# LAN_WIZ_V0_1a.net
KiCad netlist of a schematic drawn in EAGLE
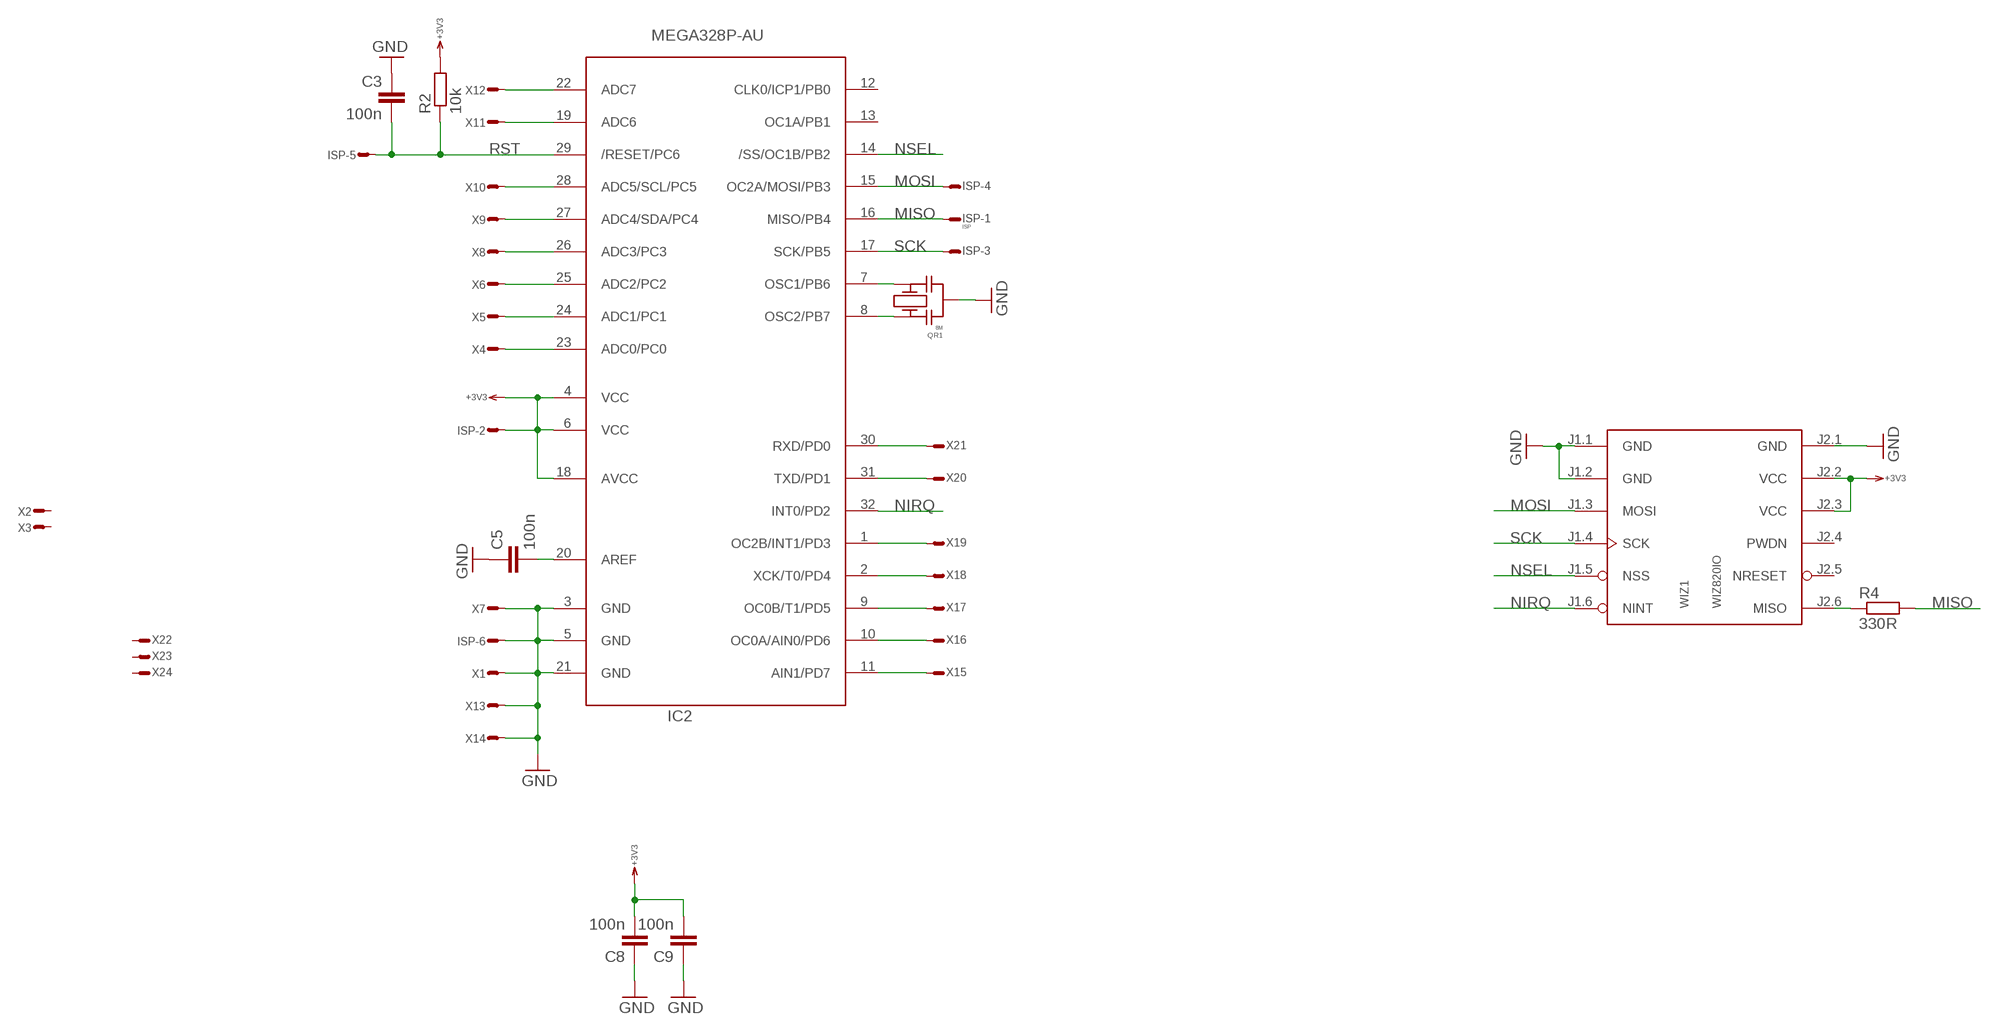
[diagram p0: schematic, sheet 1]

(export (version "E")
  (design (tool "Eeschema 10.0.6"))
  (components
    (comp (ref "C3")
      (value "100n")
      (footprint "eagle-import:0603")
      (libsource (lib "eagle-import") (part "C0603"))
    )
    (comp (ref "C5")
      (value "100n")
      (footprint "eagle-import:0603")
      (libsource (lib "eagle-import") (part "C0603"))
    )
    (comp (ref "C8")
      (value "100n")
      (footprint "eagle-import:0603")
      (libsource (lib "eagle-import") (part "C0603"))
    )
    (comp (ref "C9")
      (value "100n")
      (footprint "eagle-import:0603")
      (libsource (lib "eagle-import") (part "C0603"))
    )
    (comp (ref "IC2")
      (value "MEGA328P-AU")
      (footprint "eagle-import:TQFP32-08")
      (libsource (lib "eagle-import") (part "MEGA168PA"))
    )
    (comp (ref "ISP")
      (value "ISP")
      (footprint "eagle-import:ML6S")
      (libsource (lib "eagle-import") (part "ML6ES"))
    )
    (comp (ref "QR1")
      (value "8M")
      (footprint "eagle-import:CR")
      (libsource (lib "eagle-import") (part "QRCR"))
    )
    (comp (ref "R2")
      (value "10k")
      (footprint "eagle-import:0603")
      (libsource (lib "eagle-import") (part "R0603"))
    )
    (comp (ref "R4")
      (value "330R")
      (footprint "eagle-import:0603")
      (libsource (lib "eagle-import") (part "R0603"))
    )
    (comp (ref "WIZ1")
      (value "WIZ820IO")
      (footprint "eagle-import:WIZ820IO")
      (libsource (lib "eagle-import") (part "WIZ820IO"))
    )
    (comp (ref "X1")
      (value "WIREPADT1.6/0.9")
      (footprint "eagle-import:T1.6_0.9")
      (libsource (lib "eagle-import") (part "WIREPADT1.6/0.9"))
    )
    (comp (ref "X2")
      (value "WIREPADT1.6/0.9")
      (footprint "eagle-import:T1.6_0.9")
      (libsource (lib "eagle-import") (part "WIREPADT1.6/0.9"))
    )
    (comp (ref "X3")
      (value "WIREPADT1.6/0.9")
      (footprint "eagle-import:T1.6_0.9")
      (libsource (lib "eagle-import") (part "WIREPADT1.6/0.9"))
    )
    (comp (ref "X4")
      (value "WIREPADT1.6/0.9")
      (footprint "eagle-import:T1.6_0.9")
      (libsource (lib "eagle-import") (part "WIREPADT1.6/0.9"))
    )
    (comp (ref "X5")
      (value "WIREPADT1.6/0.9")
      (footprint "eagle-import:T1.6_0.9")
      (libsource (lib "eagle-import") (part "WIREPADT1.6/0.9"))
    )
    (comp (ref "X6")
      (value "WIREPADT1.6/0.9")
      (footprint "eagle-import:T1.6_0.9")
      (libsource (lib "eagle-import") (part "WIREPADT1.6/0.9"))
    )
    (comp (ref "X7")
      (value "WIREPADT1.6/0.9")
      (footprint "eagle-import:T1.6_0.9")
      (libsource (lib "eagle-import") (part "WIREPADT1.6/0.9"))
    )
    (comp (ref "X8")
      (value "WIREPADT1.6/0.9")
      (footprint "eagle-import:T1.6_0.9")
      (libsource (lib "eagle-import") (part "WIREPADT1.6/0.9"))
    )
    (comp (ref "X9")
      (value "WIREPADT1.6/0.9")
      (footprint "eagle-import:T1.6_0.9")
      (libsource (lib "eagle-import") (part "WIREPADT1.6/0.9"))
    )
    (comp (ref "X10")
      (value "WIREPADT1.6/0.9")
      (footprint "eagle-import:T1.6_0.9")
      (libsource (lib "eagle-import") (part "WIREPADT1.6/0.9"))
    )
    (comp (ref "X11")
      (value "WIREPADT1.6/0.9")
      (footprint "eagle-import:T1.6_0.9")
      (libsource (lib "eagle-import") (part "WIREPADT1.6/0.9"))
    )
    (comp (ref "X12")
      (value "WIREPADT1.6/0.9")
      (footprint "eagle-import:T1.6_0.9")
      (libsource (lib "eagle-import") (part "WIREPADT1.6/0.9"))
    )
    (comp (ref "X13")
      (value "WIREPADT1.6/0.9")
      (footprint "eagle-import:T1.6_0.9")
      (libsource (lib "eagle-import") (part "WIREPADT1.6/0.9"))
    )
    (comp (ref "X14")
      (value "WIREPADT1.6/0.9")
      (footprint "eagle-import:T1.6_0.9")
      (libsource (lib "eagle-import") (part "WIREPADT1.6/0.9"))
    )
    (comp (ref "X15")
      (value "WIREPADT1.6/0.9")
      (footprint "eagle-import:T1.6_0.9")
      (libsource (lib "eagle-import") (part "WIREPADT1.6/0.9"))
    )
    (comp (ref "X16")
      (value "WIREPADT1.6/0.9")
      (footprint "eagle-import:T1.6_0.9")
      (libsource (lib "eagle-import") (part "WIREPADT1.6/0.9"))
    )
    (comp (ref "X17")
      (value "WIREPADT1.6/0.9")
      (footprint "eagle-import:T1.6_0.9")
      (libsource (lib "eagle-import") (part "WIREPADT1.6/0.9"))
    )
    (comp (ref "X18")
      (value "WIREPADT1.6/0.9")
      (footprint "eagle-import:T1.6_0.9")
      (libsource (lib "eagle-import") (part "WIREPADT1.6/0.9"))
    )
    (comp (ref "X19")
      (value "WIREPADT1.6/0.9")
      (footprint "eagle-import:T1.6_0.9")
      (libsource (lib "eagle-import") (part "WIREPADT1.6/0.9"))
    )
    (comp (ref "X20")
      (value "WIREPADT1.6/0.9")
      (footprint "eagle-import:T1.6_0.9")
      (libsource (lib "eagle-import") (part "WIREPADT1.6/0.9"))
    )
    (comp (ref "X21")
      (value "WIREPADT1.6/0.9")
      (footprint "eagle-import:T1.6_0.9")
      (libsource (lib "eagle-import") (part "WIREPADT1.6/0.9"))
    )
    (comp (ref "X22")
      (value "WIREPADT1.6/0.9")
      (footprint "eagle-import:T1.6_0.9")
      (libsource (lib "eagle-import") (part "WIREPADT1.6/0.9"))
    )
    (comp (ref "X23")
      (value "WIREPADT1.6/0.9")
      (footprint "eagle-import:T1.6_0.9")
      (libsource (lib "eagle-import") (part "WIREPADT1.6/0.9"))
    )
    (comp (ref "X24")
      (value "WIREPADT1.6/0.9")
      (footprint "eagle-import:T1.6_0.9")
      (libsource (lib "eagle-import") (part "WIREPADT1.6/0.9"))
    )
  )
  (nets
    (net (code "1") (name "+3V3") (class "Default")
      (node (ref "C8") (pin "2") (pinfunction "2_2") (pintype "passive"))
      (node (ref "C9") (pin "2") (pinfunction "2_2") (pintype "passive"))
      (node (ref "IC2") (pin "18") (pinfunction "AVCC_18") (pintype "bidirectional"))
      (node (ref "IC2") (pin "4") (pinfunction "VCC_4") (pintype "bidirectional"))
      (node (ref "IC2") (pin "6") (pinfunction "VCC_6") (pintype "bidirectional"))
      (node (ref "ISP") (pin "2") (pinfunction "S_2") (pintype "passive"))
      (node (ref "R2") (pin "2") (pinfunction "2_2") (pintype "passive"))
      (node (ref "WIZ1") (pin "J2.2") (pinfunction "VCC_J2.2") (pintype "bidirectional"))
      (node (ref "WIZ1") (pin "J2.3") (pinfunction "VCC_J2.3") (pintype "bidirectional"))
    )
    (net (code "2") (name "/MISO") (class "Default")
      (node (ref "IC2") (pin "16") (pinfunction "MISO/PB4_16") (pintype "bidirectional"))
      (node (ref "ISP") (pin "1") (pinfunction "S_1") (pintype "passive"))
      (node (ref "R4") (pin "2") (pinfunction "2_2") (pintype "passive"))
    )
    (net (code "3") (name "/MOSI") (class "Default")
      (node (ref "IC2") (pin "15") (pinfunction "OC2A/MOSI/PB3_15") (pintype "bidirectional"))
      (node (ref "ISP") (pin "4") (pinfunction "S_4") (pintype "passive"))
      (node (ref "WIZ1") (pin "J1.3") (pinfunction "MOSI_J1.3") (pintype "input"))
    )
    (net (code "4") (name "/NIRQ") (class "Default")
      (node (ref "IC2") (pin "32") (pinfunction "INT0/PD2_32") (pintype "bidirectional"))
      (node (ref "WIZ1") (pin "J1.6") (pinfunction "NINT_J1.6") (pintype "output"))
    )
    (net (code "5") (name "/NSEL") (class "Default")
      (node (ref "IC2") (pin "14") (pinfunction "/SS/OC1B/PB2_14") (pintype "bidirectional"))
      (node (ref "WIZ1") (pin "J1.5") (pinfunction "NSS_J1.5") (pintype "input"))
    )
    (net (code "6") (name "/RST") (class "Default")
      (node (ref "C3") (pin "2") (pinfunction "2_2") (pintype "passive"))
      (node (ref "IC2") (pin "29") (pinfunction "/RESET/PC6_29") (pintype "bidirectional"))
      (node (ref "ISP") (pin "5") (pinfunction "S_5") (pintype "passive"))
      (node (ref "R2") (pin "1") (pinfunction "1_1") (pintype "passive"))
    )
    (net (code "7") (name "/SCK") (class "Default")
      (node (ref "IC2") (pin "17") (pinfunction "SCK/PB5_17") (pintype "bidirectional"))
      (node (ref "ISP") (pin "3") (pinfunction "S_3") (pintype "passive"))
      (node (ref "WIZ1") (pin "J1.4") (pinfunction "SCK_J1.4") (pintype "input"))
    )
    (net (code "8") (name "GND") (class "Default")
      (node (ref "C3") (pin "1") (pinfunction "1_1") (pintype "passive"))
      (node (ref "C5") (pin "1") (pinfunction "1_1") (pintype "passive"))
      (node (ref "C8") (pin "1") (pinfunction "1_1") (pintype "passive"))
      (node (ref "C9") (pin "1") (pinfunction "1_1") (pintype "passive"))
      (node (ref "IC2") (pin "21") (pinfunction "GND_21") (pintype "bidirectional"))
      (node (ref "IC2") (pin "3") (pinfunction "GND_3") (pintype "bidirectional"))
      (node (ref "IC2") (pin "5") (pinfunction "GND_5") (pintype "bidirectional"))
      (node (ref "ISP") (pin "6") (pinfunction "S_6") (pintype "passive"))
      (node (ref "QR1") (pin "M") (pinfunction "M_M") (pintype "passive"))
      (node (ref "WIZ1") (pin "J1.1") (pinfunction "GND_J1.1") (pintype "bidirectional"))
      (node (ref "WIZ1") (pin "J1.2") (pinfunction "GND_J1.2") (pintype "bidirectional"))
      (node (ref "WIZ1") (pin "J2.1") (pinfunction "GND_J2.1") (pintype "bidirectional"))
      (node (ref "X1") (pin "1") (pinfunction "S_1") (pintype "passive"))
      (node (ref "X13") (pin "1") (pinfunction "S_1") (pintype "passive"))
      (node (ref "X14") (pin "1") (pinfunction "S_1") (pintype "passive"))
      (node (ref "X7") (pin "1") (pinfunction "S_1") (pintype "passive"))
    )
    (net (code "9") (name "Net-(IC2-ADC0{slash}PC0)") (class "Default")
      (node (ref "IC2") (pin "23") (pinfunction "ADC0/PC0_23") (pintype "bidirectional"))
      (node (ref "X4") (pin "1") (pinfunction "S_1") (pintype "passive"))
    )
    (net (code "10") (name "Net-(IC2-ADC1{slash}PC1)") (class "Default")
      (node (ref "IC2") (pin "24") (pinfunction "ADC1/PC1_24") (pintype "bidirectional"))
      (node (ref "X5") (pin "1") (pinfunction "S_1") (pintype "passive"))
    )
    (net (code "11") (name "Net-(IC2-ADC2{slash}PC2)") (class "Default")
      (node (ref "IC2") (pin "25") (pinfunction "ADC2/PC2_25") (pintype "bidirectional"))
      (node (ref "X6") (pin "1") (pinfunction "S_1") (pintype "passive"))
    )
    (net (code "12") (name "Net-(IC2-ADC3{slash}PC3)") (class "Default")
      (node (ref "IC2") (pin "26") (pinfunction "ADC3/PC3_26") (pintype "bidirectional"))
      (node (ref "X8") (pin "1") (pinfunction "S_1") (pintype "passive"))
    )
    (net (code "13") (name "Net-(IC2-ADC4{slash}SDA{slash}PC4)") (class "Default")
      (node (ref "IC2") (pin "27") (pinfunction "ADC4/SDA/PC4_27") (pintype "bidirectional"))
      (node (ref "X9") (pin "1") (pinfunction "S_1") (pintype "passive"))
    )
    (net (code "14") (name "Net-(IC2-ADC5{slash}SCL{slash}PC5)") (class "Default")
      (node (ref "IC2") (pin "28") (pinfunction "ADC5/SCL/PC5_28") (pintype "bidirectional"))
      (node (ref "X10") (pin "1") (pinfunction "S_1") (pintype "passive"))
    )
    (net (code "15") (name "Net-(IC2-ADC6)") (class "Default")
      (node (ref "IC2") (pin "19") (pinfunction "ADC6_19") (pintype "bidirectional"))
      (node (ref "X11") (pin "1") (pinfunction "S_1") (pintype "passive"))
    )
    (net (code "16") (name "Net-(IC2-ADC7)") (class "Default")
      (node (ref "IC2") (pin "22") (pinfunction "ADC7_22") (pintype "bidirectional"))
      (node (ref "X12") (pin "1") (pinfunction "S_1") (pintype "passive"))
    )
    (net (code "17") (name "Net-(IC2-AIN1{slash}PD7)") (class "Default")
      (node (ref "IC2") (pin "11") (pinfunction "AIN1/PD7_11") (pintype "bidirectional"))
      (node (ref "X15") (pin "1") (pinfunction "S_1") (pintype "passive"))
    )
    (net (code "18") (name "Net-(IC2-AREF)") (class "Default")
      (node (ref "C5") (pin "2") (pinfunction "2_2") (pintype "passive"))
      (node (ref "IC2") (pin "20") (pinfunction "AREF_20") (pintype "bidirectional"))
    )
    (net (code "19") (name "Net-(IC2-OC0A{slash}AIN0{slash}PD6)") (class "Default")
      (node (ref "IC2") (pin "10") (pinfunction "OC0A/AIN0/PD6_10") (pintype "bidirectional"))
      (node (ref "X16") (pin "1") (pinfunction "S_1") (pintype "passive"))
    )
    (net (code "20") (name "Net-(IC2-OC0B{slash}T1{slash}PD5)") (class "Default")
      (node (ref "IC2") (pin "9") (pinfunction "OC0B/T1/PD5_9") (pintype "bidirectional"))
      (node (ref "X17") (pin "1") (pinfunction "S_1") (pintype "passive"))
    )
    (net (code "21") (name "Net-(IC2-OC2B{slash}INT1{slash}PD3)") (class "Default")
      (node (ref "IC2") (pin "1") (pinfunction "OC2B/INT1/PD3_1") (pintype "bidirectional"))
      (node (ref "X19") (pin "1") (pinfunction "S_1") (pintype "passive"))
    )
    (net (code "22") (name "Net-(IC2-OSC1{slash}PB6)") (class "Default")
      (node (ref "IC2") (pin "7") (pinfunction "OSC1/PB6_7") (pintype "bidirectional"))
      (node (ref "QR1") (pin "2") (pinfunction "2_2") (pintype "passive"))
    )
    (net (code "23") (name "Net-(IC2-OSC2{slash}PB7)") (class "Default")
      (node (ref "IC2") (pin "8") (pinfunction "OSC2/PB7_8") (pintype "bidirectional"))
      (node (ref "QR1") (pin "1") (pinfunction "1_1") (pintype "passive"))
    )
    (net (code "24") (name "Net-(IC2-RXD{slash}PD0)") (class "Default")
      (node (ref "IC2") (pin "30") (pinfunction "RXD/PD0_30") (pintype "bidirectional"))
      (node (ref "X21") (pin "1") (pinfunction "S_1") (pintype "passive"))
    )
    (net (code "25") (name "Net-(IC2-TXD{slash}PD1)") (class "Default")
      (node (ref "IC2") (pin "31") (pinfunction "TXD/PD1_31") (pintype "bidirectional"))
      (node (ref "X20") (pin "1") (pinfunction "S_1") (pintype "passive"))
    )
    (net (code "26") (name "Net-(IC2-XCK{slash}T0{slash}PD4)") (class "Default")
      (node (ref "IC2") (pin "2") (pinfunction "XCK/T0/PD4_2") (pintype "bidirectional"))
      (node (ref "X18") (pin "1") (pinfunction "S_1") (pintype "passive"))
    )
    (net (code "27") (name "Net-(WIZ1-MISO)") (class "Default")
      (node (ref "R4") (pin "1") (pinfunction "1_1") (pintype "passive"))
      (node (ref "WIZ1") (pin "J2.6") (pinfunction "MISO_J2.6") (pintype "output"))
    )
    (net (code "28") (name "unconnected-(IC2-CLK0{slash}ICP1{slash}PB0-Pad12)") (class "Default")
      (node (ref "IC2") (pin "12") (pinfunction "CLK0/ICP1/PB0_12") (pintype "bidirectional"))
    )
    (net (code "29") (name "unconnected-(IC2-OC1A{slash}PB1-Pad13)") (class "Default")
      (node (ref "IC2") (pin "13") (pinfunction "OC1A/PB1_13") (pintype "bidirectional"))
    )
    (net (code "30") (name "unconnected-(WIZ1-NRESET-PadJ2.5)") (class "Default")
      (node (ref "WIZ1") (pin "J2.5") (pinfunction "NRESET_J2.5") (pintype "input"))
    )
    (net (code "31") (name "unconnected-(WIZ1-PWDN-PadJ2.4)") (class "Default")
      (node (ref "WIZ1") (pin "J2.4") (pinfunction "PWDN_J2.4") (pintype "input"))
    )
    (net (code "32") (name "unconnected-(X2-S-Pad1)") (class "Default")
      (node (ref "X2") (pin "1") (pinfunction "S_1") (pintype "passive"))
    )
    (net (code "33") (name "unconnected-(X3-S-Pad1)") (class "Default")
      (node (ref "X3") (pin "1") (pinfunction "S_1") (pintype "passive"))
    )
    (net (code "34") (name "unconnected-(X22-S-Pad1)") (class "Default")
      (node (ref "X22") (pin "1") (pinfunction "S_1") (pintype "passive"))
    )
    (net (code "35") (name "unconnected-(X23-S-Pad1)") (class "Default")
      (node (ref "X23") (pin "1") (pinfunction "S_1") (pintype "passive"))
    )
    (net (code "36") (name "unconnected-(X24-S-Pad1)") (class "Default")
      (node (ref "X24") (pin "1") (pinfunction "S_1") (pintype "passive"))
    )
  )
)
